# analog.net
KiCad netlist of a schematic drawn in Altium Designer
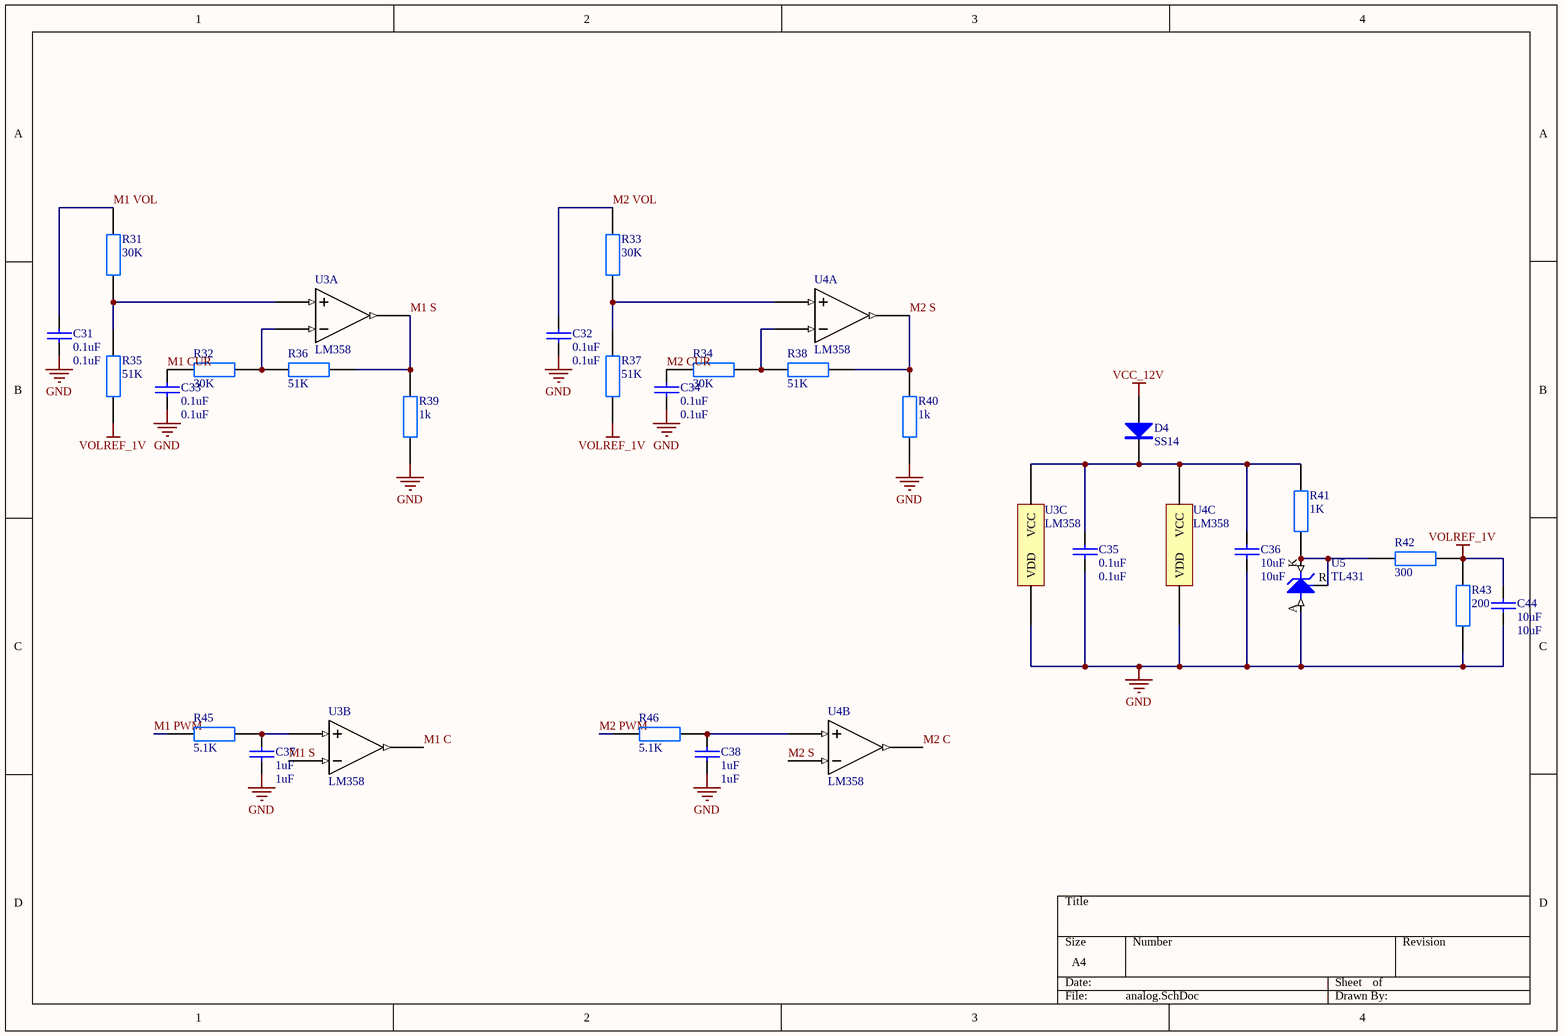
[diagram p0: analog.SchDoc]

(export (version "E")
  (design (tool "Eeschema 10.0.6"))
  (components
    (comp (ref "C31")
      (value "0.1uF")
      (footprint "0805 CAP")
      (fields (field (name "ALTIUM_VALUE") "0.1uF"))
      (libsource (lib "common") (part "CAP"))
    )
    (comp (ref "C32")
      (value "0.1uF")
      (footprint "0805 CAP")
      (fields (field (name "ALTIUM_VALUE") "0.1uF"))
      (libsource (lib "common") (part "CAP"))
    )
    (comp (ref "C33")
      (value "0.1uF")
      (footprint "0805 CAP")
      (fields (field (name "ALTIUM_VALUE") "0.1uF"))
      (libsource (lib "common") (part "CAP"))
    )
    (comp (ref "C34")
      (value "0.1uF")
      (footprint "0805 CAP")
      (fields (field (name "ALTIUM_VALUE") "0.1uF"))
      (libsource (lib "common") (part "CAP"))
    )
    (comp (ref "C35")
      (value "0.1uF")
      (footprint "0805 CAP")
      (fields (field (name "ALTIUM_VALUE") "0.1uF"))
      (libsource (lib "common") (part "CAP"))
    )
    (comp (ref "C36")
      (value "10uF")
      (footprint "0805 CAP")
      (fields (field (name "ALTIUM_VALUE") "10uF"))
      (libsource (lib "common") (part "CAP"))
    )
    (comp (ref "C37")
      (value "1uF")
      (footprint "0805 CAP")
      (fields (field (name "ALTIUM_VALUE") "1uF"))
      (libsource (lib "common") (part "CAP"))
    )
    (comp (ref "C38")
      (value "1uF")
      (footprint "0805 CAP")
      (fields (field (name "ALTIUM_VALUE") "1uF"))
      (libsource (lib "common") (part "CAP"))
    )
    (comp (ref "C44")
      (value "10uF")
      (footprint "0805 CAP")
      (fields (field (name "ALTIUM_VALUE") "10uF"))
      (libsource (lib "common") (part "CAP"))
    )
    (comp (ref "D4")
      (value "SS14")
      (footprint "SMA")
      (description "Diode")
      (libsource (lib "common") (part "SS14"))
    )
    (comp (ref "R31")
      (value "30K")
      (footprint "0805")
      (description "RES")
      (libsource (lib "common") (part "RES"))
    )
    (comp (ref "R32")
      (value "30K")
      (footprint "0805")
      (description "RES")
      (libsource (lib "common") (part "RES"))
    )
    (comp (ref "R33")
      (value "30K")
      (footprint "0805")
      (description "RES")
      (libsource (lib "common") (part "RES"))
    )
    (comp (ref "R34")
      (value "30K")
      (footprint "0805")
      (description "RES")
      (libsource (lib "common") (part "RES"))
    )
    (comp (ref "R35")
      (value "51K")
      (footprint "0805")
      (description "RES")
      (libsource (lib "common") (part "RES"))
    )
    (comp (ref "R36")
      (value "51K")
      (footprint "0805")
      (description "RES")
      (libsource (lib "common") (part "RES"))
    )
    (comp (ref "R37")
      (value "51K")
      (footprint "0805")
      (description "RES")
      (libsource (lib "common") (part "RES"))
    )
    (comp (ref "R38")
      (value "51K")
      (footprint "0805")
      (description "RES")
      (libsource (lib "common") (part "RES"))
    )
    (comp (ref "R39")
      (value "1k")
      (footprint "0805")
      (description "RES")
      (libsource (lib "common") (part "RES"))
    )
    (comp (ref "R40")
      (value "1k")
      (footprint "0805")
      (description "RES")
      (libsource (lib "common") (part "RES"))
    )
    (comp (ref "R41")
      (value "1K")
      (footprint "0805")
      (description "RES")
      (libsource (lib "common") (part "RES"))
    )
    (comp (ref "R42")
      (value "300")
      (footprint "0805")
      (description "RES")
      (libsource (lib "common") (part "RES"))
    )
    (comp (ref "R43")
      (value "200")
      (footprint "0805")
      (description "RES")
      (libsource (lib "common") (part "RES"))
    )
    (comp (ref "R45")
      (value "5.1K")
      (footprint "0805")
      (description "RES")
      (libsource (lib "common") (part "RES"))
    )
    (comp (ref "R46")
      (value "5.1K")
      (footprint "0805")
      (description "RES")
      (libsource (lib "common") (part "RES"))
    )
    (comp (ref "U3") (value "LM358") (footprint "so-8") (libsource (lib "") (part "LM358_1")))
    (comp (ref "U4") (value "LM358") (footprint "so-8") (libsource (lib "") (part "LM358_1")))
    (comp (ref "U5")
      (value "TL431")
      (footprint "sot-23")
      (description "IC")
      (libsource (lib "common") (part "TL431"))
    )
  )
  (nets
    (net (code "1") (name "/M1 C") (class "Default")
      (node (ref "U3") (pin "7") (pinfunction "7_7") (pintype "output"))
    )
    (net (code "2") (name "/M1 CUR") (class "Default")
      (node (ref "C33") (pin "1") (pinfunction "1_1") (pintype "passive"))
      (node (ref "R32") (pin "2") (pinfunction "2_2") (pintype "passive"))
    )
    (net (code "3") (name "/M1 PWM") (class "Default")
      (node (ref "R45") (pin "1") (pinfunction "1_1") (pintype "passive"))
    )
    (net (code "4") (name "/M1 S") (class "Default")
      (node (ref "R36") (pin "1") (pinfunction "1_1") (pintype "passive"))
      (node (ref "R39") (pin "2") (pinfunction "2_2") (pintype "passive"))
      (node (ref "U3") (pin "1") (pinfunction "1_1") (pintype "output"))
      (node (ref "U3") (pin "6") (pinfunction "6_6") (pintype "input"))
    )
    (net (code "5") (name "/M1 VOL") (class "Default")
      (node (ref "C31") (pin "1") (pinfunction "1_1") (pintype "passive"))
      (node (ref "R31") (pin "2") (pinfunction "2_2") (pintype "passive"))
    )
    (net (code "6") (name "/M2 C") (class "Default")
      (node (ref "U4") (pin "7") (pinfunction "7_7") (pintype "output"))
    )
    (net (code "7") (name "/M2 CUR") (class "Default")
      (node (ref "C34") (pin "1") (pinfunction "1_1") (pintype "passive"))
      (node (ref "R34") (pin "2") (pinfunction "2_2") (pintype "passive"))
    )
    (net (code "8") (name "/M2 PWM") (class "Default")
      (node (ref "R46") (pin "1") (pinfunction "1_1") (pintype "passive"))
    )
    (net (code "9") (name "/M2 S") (class "Default")
      (node (ref "R38") (pin "1") (pinfunction "1_1") (pintype "passive"))
      (node (ref "R40") (pin "2") (pinfunction "2_2") (pintype "passive"))
      (node (ref "U4") (pin "1") (pinfunction "1_1") (pintype "output"))
      (node (ref "U4") (pin "6") (pinfunction "6_6") (pintype "input"))
    )
    (net (code "10") (name "/M2 VOL") (class "Default")
      (node (ref "C32") (pin "1") (pinfunction "1_1") (pintype "passive"))
      (node (ref "R33") (pin "2") (pinfunction "2_2") (pintype "passive"))
    )
    (net (code "11") (name "GND") (class "Default")
      (node (ref "C31") (pin "2") (pinfunction "2_2") (pintype "passive"))
      (node (ref "C32") (pin "2") (pinfunction "2_2") (pintype "passive"))
      (node (ref "C33") (pin "2") (pinfunction "2_2") (pintype "passive"))
      (node (ref "C34") (pin "2") (pinfunction "2_2") (pintype "passive"))
      (node (ref "C35") (pin "2") (pinfunction "2_2") (pintype "passive"))
      (node (ref "C36") (pin "2") (pinfunction "2_2") (pintype "passive"))
      (node (ref "C37") (pin "2") (pinfunction "2_2") (pintype "passive"))
      (node (ref "C38") (pin "2") (pinfunction "2_2") (pintype "passive"))
      (node (ref "C44") (pin "2") (pinfunction "2_2") (pintype "passive"))
      (node (ref "R39") (pin "1") (pinfunction "1_1") (pintype "passive"))
      (node (ref "R40") (pin "1") (pinfunction "1_1") (pintype "passive"))
      (node (ref "R43") (pin "1") (pinfunction "1_1") (pintype "passive"))
      (node (ref "U3") (pin "4") (pinfunction "VDD_4") (pintype "power_in"))
      (node (ref "U4") (pin "4") (pinfunction "VDD_4") (pintype "power_in"))
      (node (ref "U5") (pin "A") (pinfunction "A_A") (pintype "input"))
    )
    (net (code "12") (name "Net-(C37-Pad1)") (class "Default")
      (node (ref "C37") (pin "1") (pinfunction "1_1") (pintype "passive"))
      (node (ref "R45") (pin "2") (pinfunction "2_2") (pintype "passive"))
      (node (ref "U3") (pin "5") (pinfunction "5_5") (pintype "input"))
    )
    (net (code "13") (name "Net-(C38-Pad1)") (class "Default")
      (node (ref "C38") (pin "1") (pinfunction "1_1") (pintype "passive"))
      (node (ref "R46") (pin "2") (pinfunction "2_2") (pintype "passive"))
      (node (ref "U4") (pin "5") (pinfunction "5_5") (pintype "input"))
    )
    (net (code "14") (name "Net-(D4-K)") (class "Default")
      (node (ref "C35") (pin "1") (pinfunction "1_1") (pintype "passive"))
      (node (ref "C36") (pin "1") (pinfunction "1_1") (pintype "passive"))
      (node (ref "D4") (pin "2") (pinfunction "K_2") (pintype "passive"))
      (node (ref "R41") (pin "2") (pinfunction "2_2") (pintype "passive"))
      (node (ref "U3") (pin "8") (pinfunction "VCC_8") (pintype "power_in"))
      (node (ref "U4") (pin "8") (pinfunction "VCC_8") (pintype "power_in"))
    )
    (net (code "15") (name "Net-(R31-Pad1)") (class "Default")
      (node (ref "R31") (pin "1") (pinfunction "1_1") (pintype "passive"))
      (node (ref "R35") (pin "2") (pinfunction "2_2") (pintype "passive"))
      (node (ref "U3") (pin "3") (pinfunction "3_3") (pintype "input"))
    )
    (net (code "16") (name "Net-(R32-Pad1)") (class "Default")
      (node (ref "R32") (pin "1") (pinfunction "1_1") (pintype "passive"))
      (node (ref "R36") (pin "2") (pinfunction "2_2") (pintype "passive"))
      (node (ref "U3") (pin "2") (pinfunction "2_2") (pintype "input"))
    )
    (net (code "17") (name "Net-(R33-Pad1)") (class "Default")
      (node (ref "R33") (pin "1") (pinfunction "1_1") (pintype "passive"))
      (node (ref "R37") (pin "2") (pinfunction "2_2") (pintype "passive"))
      (node (ref "U4") (pin "3") (pinfunction "3_3") (pintype "input"))
    )
    (net (code "18") (name "Net-(R34-Pad1)") (class "Default")
      (node (ref "R34") (pin "1") (pinfunction "1_1") (pintype "passive"))
      (node (ref "R38") (pin "2") (pinfunction "2_2") (pintype "passive"))
      (node (ref "U4") (pin "2") (pinfunction "2_2") (pintype "input"))
    )
    (net (code "19") (name "Net-(R41-Pad1)") (class "Default")
      (node (ref "R41") (pin "1") (pinfunction "1_1") (pintype "passive"))
      (node (ref "R42") (pin "2") (pinfunction "2_2") (pintype "passive"))
      (node (ref "U5") (pin "K") (pinfunction "K_K") (pintype "input"))
      (node (ref "U5") (pin "R") (pinfunction "R_R") (pintype "passive"))
    )
    (net (code "20") (name "VCC_12V") (class "Default")
      (node (ref "D4") (pin "1") (pinfunction "A_1") (pintype "passive"))
    )
    (net (code "21") (name "VOLREF_1V") (class "Default")
      (node (ref "C44") (pin "1") (pinfunction "1_1") (pintype "passive"))
      (node (ref "R35") (pin "1") (pinfunction "1_1") (pintype "passive"))
      (node (ref "R37") (pin "1") (pinfunction "1_1") (pintype "passive"))
      (node (ref "R42") (pin "1") (pinfunction "1_1") (pintype "passive"))
      (node (ref "R43") (pin "2") (pinfunction "2_2") (pintype "passive"))
    )
  )
)
